# Sheet1.net
KiCad netlist of a schematic drawn in Altium Designer
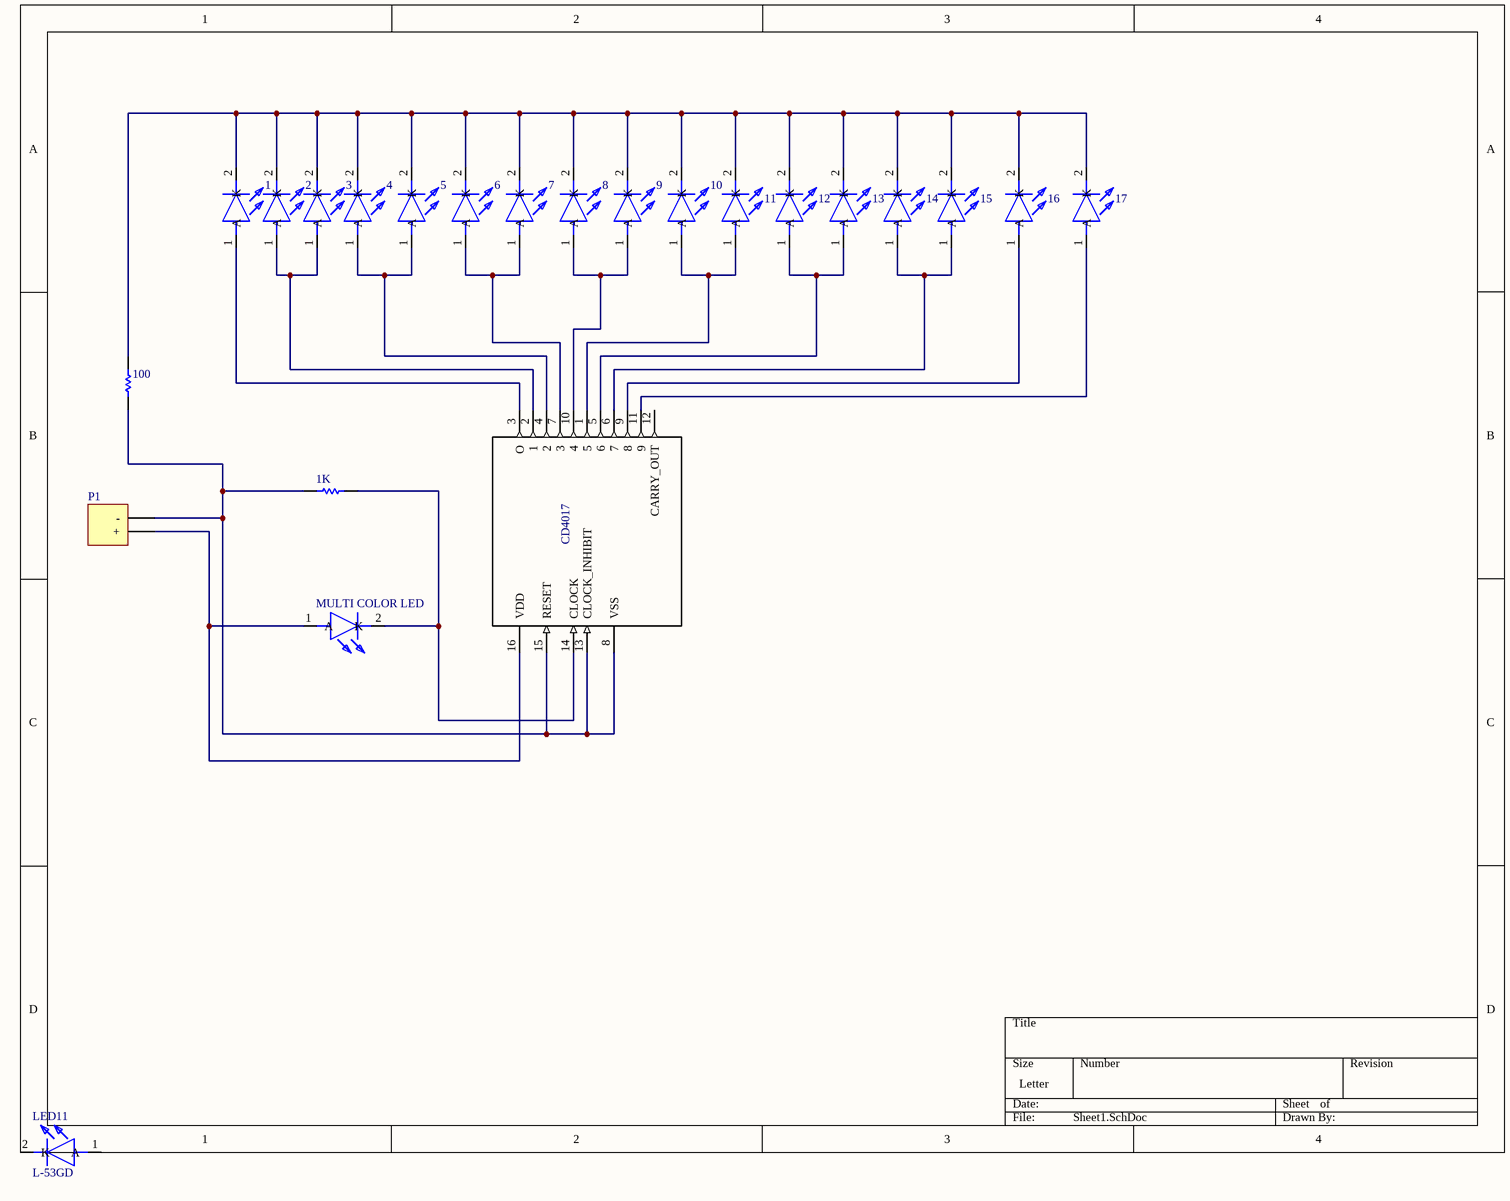
[diagram p0: Sheet1.SchDoc]

(export (version "E")
  (design (tool "Eeschema 10.0.6"))
  (components
    (comp (ref "1")
      (value "L-53GD")
      (footprint "SamacSys:L-53GD")
      (description "LED")
      (fields (field (name "RS PART NUMBER") "2286004A"))
      (libsource (lib "SamacSys") (part "L-53GD"))
    )
    (comp (ref "1K")
      (value "Res1")
      (footprint "AXIAL-0.3")
      (description "Resistor")
      (fields (field (name "PUBLISHER") "Altium Limited"))
      (libsource (lib "Miscellaneous Devices") (part "Res1"))
    )
    (comp (ref "2")
      (value "L-53GD")
      (footprint "SamacSys:L-53GD")
      (description "LED")
      (fields (field (name "RS PART NUMBER") "2286004A"))
      (libsource (lib "SamacSys") (part "L-53GD"))
    )
    (comp (ref "3")
      (value "L-53GD")
      (footprint "SamacSys:L-53GD")
      (description "LED")
      (fields (field (name "RS PART NUMBER") "2286004A"))
      (libsource (lib "SamacSys") (part "L-53GD"))
    )
    (comp (ref "4")
      (value "L-53GD")
      (footprint "SamacSys:L-53GD")
      (description "LED")
      (fields (field (name "RS PART NUMBER") "2286004A"))
      (libsource (lib "SamacSys") (part "L-53GD"))
    )
    (comp (ref "5")
      (value "L-53GD")
      (footprint "SamacSys:L-53GD")
      (description "LED")
      (fields (field (name "RS PART NUMBER") "2286004A"))
      (libsource (lib "SamacSys") (part "L-53GD"))
    )
    (comp (ref "6")
      (value "L-53GD")
      (footprint "SamacSys:L-53GD")
      (description "LED")
      (fields (field (name "RS PART NUMBER") "2286004A"))
      (libsource (lib "SamacSys") (part "L-53GD"))
    )
    (comp (ref "7")
      (value "L-53GD")
      (footprint "SamacSys:L-53GD")
      (description "LED")
      (fields (field (name "RS PART NUMBER") "2286004A"))
      (libsource (lib "SamacSys") (part "L-53GD"))
    )
    (comp (ref "8")
      (value "L-53GD")
      (footprint "SamacSys:L-53GD")
      (description "LED")
      (fields (field (name "RS PART NUMBER") "2286004A"))
      (libsource (lib "SamacSys") (part "L-53GD"))
    )
    (comp (ref "9")
      (value "L-53GD")
      (footprint "SamacSys:L-53GD")
      (description "LED")
      (fields (field (name "RS PART NUMBER") "2286004A"))
      (libsource (lib "SamacSys") (part "L-53GD"))
    )
    (comp (ref "10")
      (value "L-53GD")
      (footprint "SamacSys:L-53GD")
      (description "LED")
      (fields (field (name "RS PART NUMBER") "2286004A"))
      (libsource (lib "SamacSys") (part "L-53GD"))
    )
    (comp (ref "11")
      (value "L-53GD")
      (footprint "SamacSys:L-53GD")
      (description "LED")
      (fields (field (name "RS PART NUMBER") "2286004A"))
      (libsource (lib "SamacSys") (part "L-53GD"))
    )
    (comp (ref "12")
      (value "L-53GD")
      (footprint "SamacSys:L-53GD")
      (description "LED")
      (fields (field (name "RS PART NUMBER") "2286004A"))
      (libsource (lib "SamacSys") (part "L-53GD"))
    )
    (comp (ref "13")
      (value "L-53GD")
      (footprint "SamacSys:L-53GD")
      (description "LED")
      (fields (field (name "RS PART NUMBER") "2286004A"))
      (libsource (lib "SamacSys") (part "L-53GD"))
    )
    (comp (ref "14")
      (value "L-53GD")
      (footprint "SamacSys:L-53GD")
      (description "LED")
      (fields (field (name "RS PART NUMBER") "2286004A"))
      (libsource (lib "SamacSys") (part "L-53GD"))
    )
    (comp (ref "15")
      (value "L-53GD")
      (footprint "SamacSys:L-53GD")
      (description "LED")
      (fields (field (name "RS PART NUMBER") "2286004A"))
      (libsource (lib "SamacSys") (part "L-53GD"))
    )
    (comp (ref "16")
      (value "L-53GD")
      (footprint "SamacSys:L-53GD")
      (description "LED")
      (fields (field (name "RS PART NUMBER") "2286004A"))
      (libsource (lib "SamacSys") (part "L-53GD"))
    )
    (comp (ref "17")
      (value "L-53GD")
      (footprint "SamacSys:L-53GD")
      (description "LED")
      (fields (field (name "RS PART NUMBER") "2286004A"))
      (libsource (lib "SamacSys") (part "L-53GD"))
    )
    (comp (ref "100")
      (value "Res1")
      (footprint "AXIAL-0.3")
      (description "Resistor")
      (fields (field (name "PUBLISHER") "Altium Limited"))
      (libsource (lib "Miscellaneous Devices") (part "Res1"))
    )
    (comp (ref "CD4017")
      (value "CD4017BE")
      (footprint "*DIP254P762X508-16")
      (description "IC Mos 4017/CD4017BE HARRIS")
      (fields (field (name "MF") "Texas"))
      (libsource (lib "CD4017BE") (part "CD4017BE"))
    )
    (comp (ref "LED11")
      (value "L-53GD")
      (footprint "SamacSys:L-53GD")
      (description "LED")
      (fields (field (name "RS PART NUMBER") "2286004A"))
      (libsource (lib "*") (part "L-53GD"))
    )
    (comp (ref "MULTI COLOR LED")
      (value "L-53GD")
      (footprint "SamacSys:L-53GD")
      (description "LED")
      (fields (field (name "RS PART NUMBER") "2286004A"))
      (libsource (lib "SamacSys") (part "L-53GD"))
    )
    (comp (ref "P1")
      (value "Header 2")
      (footprint "HDR1X2")
      (description "Header, 2-Pin")
      (fields (field (name "PUBLISHER") "Altium Limited"))
      (libsource (lib "Miscellaneous Connectors") (part "Header 2"))
    )
  )
  (nets
    (net (code "1") (name "Net-(1-A)") (class "Default")
      (node (ref "1") (pin "1") (pinfunction "A_1") (pintype "passive"))
      (node (ref "CD4017") (pin "3") (pinfunction "O_3") (pintype "output"))
    )
    (net (code "2") (name "Net-(1-K)") (class "Default")
      (node (ref "1") (pin "2") (pinfunction "K_2") (pintype "passive"))
      (node (ref "10") (pin "2") (pinfunction "K_2") (pintype "passive"))
      (node (ref "100") (pin "2") (pinfunction "2_2") (pintype "passive"))
      (node (ref "11") (pin "2") (pinfunction "K_2") (pintype "passive"))
      (node (ref "12") (pin "2") (pinfunction "K_2") (pintype "passive"))
      (node (ref "13") (pin "2") (pinfunction "K_2") (pintype "passive"))
      (node (ref "14") (pin "2") (pinfunction "K_2") (pintype "passive"))
      (node (ref "15") (pin "2") (pinfunction "K_2") (pintype "passive"))
      (node (ref "16") (pin "2") (pinfunction "K_2") (pintype "passive"))
      (node (ref "17") (pin "2") (pinfunction "K_2") (pintype "passive"))
      (node (ref "2") (pin "2") (pinfunction "K_2") (pintype "passive"))
      (node (ref "3") (pin "2") (pinfunction "K_2") (pintype "passive"))
      (node (ref "4") (pin "2") (pinfunction "K_2") (pintype "passive"))
      (node (ref "5") (pin "2") (pinfunction "K_2") (pintype "passive"))
      (node (ref "6") (pin "2") (pinfunction "K_2") (pintype "passive"))
      (node (ref "7") (pin "2") (pinfunction "K_2") (pintype "passive"))
      (node (ref "8") (pin "2") (pinfunction "K_2") (pintype "passive"))
      (node (ref "9") (pin "2") (pinfunction "K_2") (pintype "passive"))
    )
    (net (code "3") (name "Net-(2-A)") (class "Default")
      (node (ref "2") (pin "1") (pinfunction "A_1") (pintype "passive"))
      (node (ref "3") (pin "1") (pinfunction "A_1") (pintype "passive"))
      (node (ref "CD4017") (pin "2") (pinfunction "1_2") (pintype "output"))
    )
    (net (code "4") (name "Net-(4-A)") (class "Default")
      (node (ref "4") (pin "1") (pinfunction "A_1") (pintype "passive"))
      (node (ref "5") (pin "1") (pinfunction "A_1") (pintype "passive"))
      (node (ref "CD4017") (pin "4") (pinfunction "2_4") (pintype "output"))
    )
    (net (code "5") (name "Net-(6-A)") (class "Default")
      (node (ref "6") (pin "1") (pinfunction "A_1") (pintype "passive"))
      (node (ref "7") (pin "1") (pinfunction "A_1") (pintype "passive"))
      (node (ref "CD4017") (pin "7") (pinfunction "3_7") (pintype "output"))
    )
    (net (code "6") (name "Net-(8-A)") (class "Default")
      (node (ref "8") (pin "1") (pinfunction "A_1") (pintype "passive"))
      (node (ref "9") (pin "1") (pinfunction "A_1") (pintype "passive"))
      (node (ref "CD4017") (pin "10") (pinfunction "4_10") (pintype "output"))
    )
    (net (code "7") (name "Net-(10-A)") (class "Default")
      (node (ref "10") (pin "1") (pinfunction "A_1") (pintype "passive"))
      (node (ref "11") (pin "1") (pinfunction "A_1") (pintype "passive"))
      (node (ref "CD4017") (pin "1") (pinfunction "5_1") (pintype "output"))
    )
    (net (code "8") (name "Net-(12-A)") (class "Default")
      (node (ref "12") (pin "1") (pinfunction "A_1") (pintype "passive"))
      (node (ref "13") (pin "1") (pinfunction "A_1") (pintype "passive"))
      (node (ref "CD4017") (pin "5") (pinfunction "6_5") (pintype "output"))
    )
    (net (code "9") (name "Net-(14-A)") (class "Default")
      (node (ref "14") (pin "1") (pinfunction "A_1") (pintype "passive"))
      (node (ref "15") (pin "1") (pinfunction "A_1") (pintype "passive"))
      (node (ref "CD4017") (pin "6") (pinfunction "7_6") (pintype "output"))
    )
    (net (code "10") (name "Net-(16-A)") (class "Default")
      (node (ref "16") (pin "1") (pinfunction "A_1") (pintype "passive"))
      (node (ref "CD4017") (pin "9") (pinfunction "8_9") (pintype "output"))
    )
    (net (code "11") (name "Net-(17-A)") (class "Default")
      (node (ref "17") (pin "1") (pinfunction "A_1") (pintype "passive"))
      (node (ref "CD4017") (pin "11") (pinfunction "9_11") (pintype "output"))
    )
    (net (code "12") (name "Net-(CD4017-CLOCK)") (class "Default")
      (node (ref "1K") (pin "2") (pinfunction "2_2") (pintype "passive"))
      (node (ref "CD4017") (pin "14") (pinfunction "CLOCK_14") (pintype "input"))
      (node (ref "MULTI COLOR LED") (pin "2") (pinfunction "K_2") (pintype "passive"))
    )
    (net (code "13") (name "Net-(CD4017-CLOCK_INHIBIT)") (class "Default")
      (node (ref "100") (pin "1") (pinfunction "1_1") (pintype "passive"))
      (node (ref "1K") (pin "1") (pinfunction "1_1") (pintype "passive"))
      (node (ref "CD4017") (pin "13") (pinfunction "CLOCK_INHIBIT_13") (pintype "input"))
      (node (ref "CD4017") (pin "15") (pinfunction "RESET_15") (pintype "input"))
      (node (ref "CD4017") (pin "8") (pinfunction "VSS_8") (pintype "power_in"))
      (node (ref "P1") (pin "2") (pinfunction "-_2") (pintype "passive"))
    )
    (net (code "14") (name "Net-(CD4017-VDD)") (class "Default")
      (node (ref "CD4017") (pin "16") (pinfunction "VDD_16") (pintype "power_in"))
      (node (ref "MULTI COLOR LED") (pin "1") (pinfunction "A_1") (pintype "passive"))
      (node (ref "P1") (pin "1") (pinfunction "+_1") (pintype "passive"))
    )
    (net (code "15") (name "unconnected-(CD4017-CARRY_OUT-Pad12)") (class "Default")
      (node (ref "CD4017") (pin "12") (pinfunction "CARRY_OUT_12") (pintype "output"))
    )
    (net (code "16") (name "unconnected-(LED11-A-Pad1)") (class "Default")
      (node (ref "LED11") (pin "1") (pinfunction "A_1") (pintype "passive"))
    )
    (net (code "17") (name "unconnected-(LED11-K-Pad2)") (class "Default")
      (node (ref "LED11") (pin "2") (pinfunction "K_2") (pintype "passive"))
    )
  )
)
